# Esquematico_TB66.net
KiCad netlist of a schematic drawn in Altium Designer
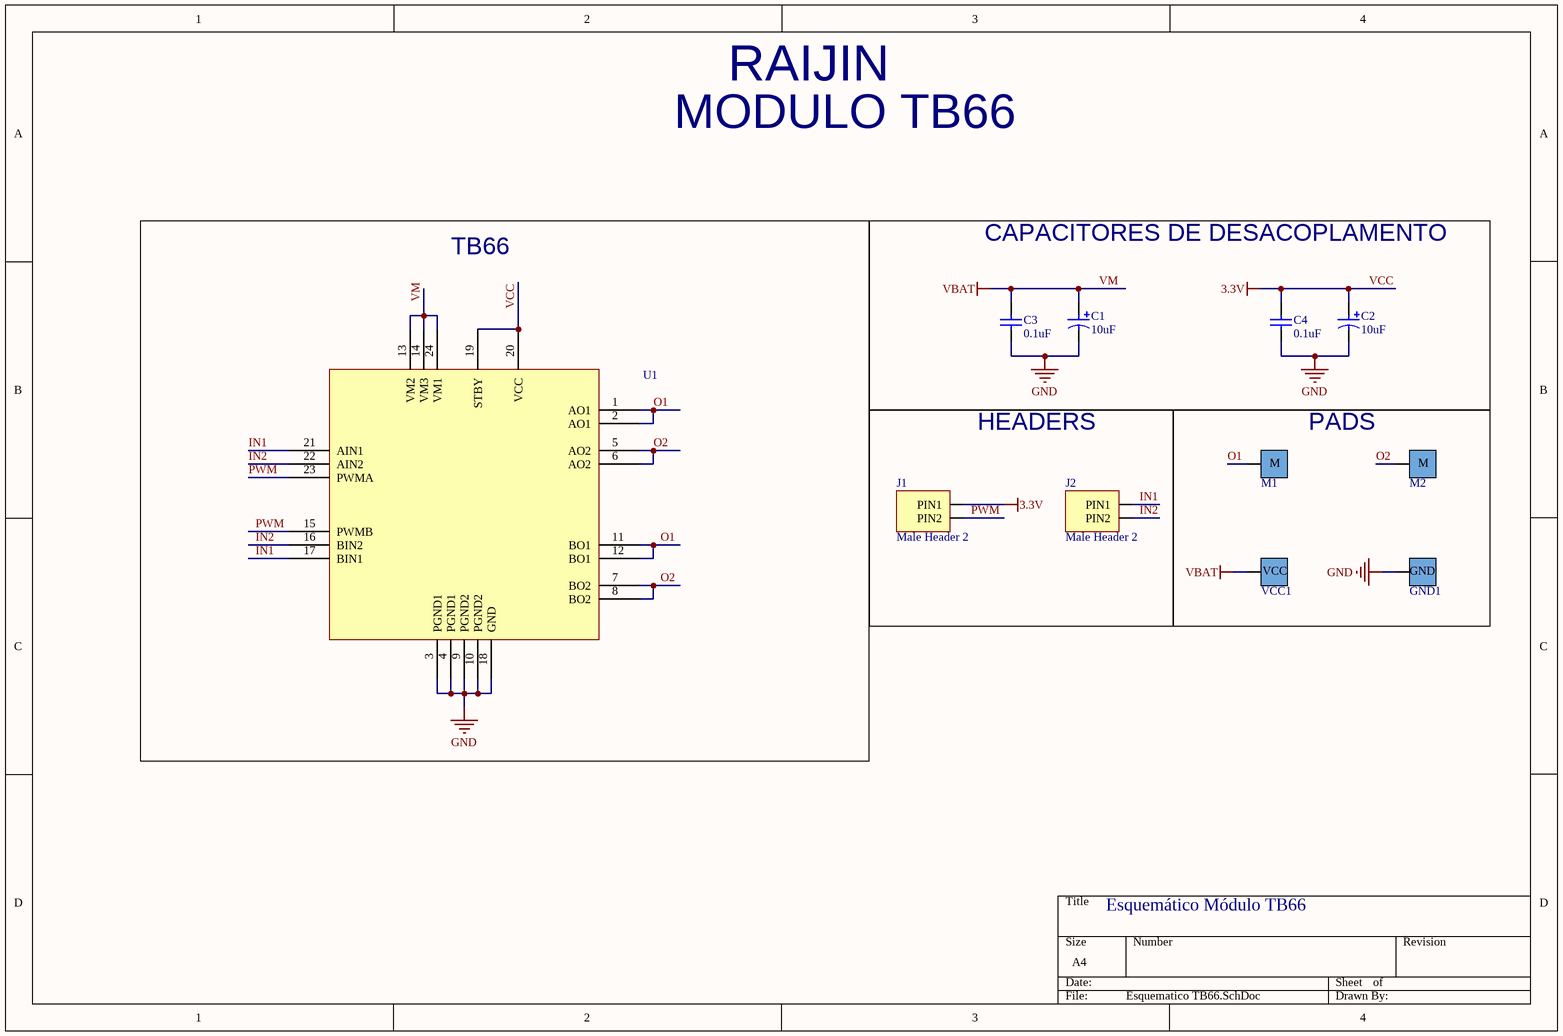
[diagram p0: Esquematico TB66.SchDoc]

(export (version "E")
  (design (tool "Eeschema 10.0.6"))
  (components
    (comp (ref "C1")
      (value "10uF")
      (footprint "TANTALUM C0805")
      (description "CAP TAN 10uF 16V 0805")
      (fields
        (field (name "MANUFACTURER") "AVX")
        (field (name "PART NUMBER") "TACR106K016RTA")
        (field (name "LIBRARY CONTROL - PERSON THAT CHECKED FOOTPRINT") "Nikaum")
        (field (name "LIBRARY CONTROL - PERSON THAT CHECKED SCHEMATIC") "Nikaum")
        (field (name "LIBRARY CONTROL - PERSON THAT DID THE LAST UPDATE FOOTPRINT") "Nikaum")
        (field (name "LIBRARY CONTROL - PERSON THAT DID THE LAST UPDATE SCHEMATIC") "Nikaum")
      )
      (libsource (lib "Uai!Tecas") (part "TACR106K016RTA"))
    )
    (comp (ref "C2")
      (value "10uF")
      (footprint "TANTALUM C0805")
      (description "CAP TAN 10uF 16V 0805")
      (fields
        (field (name "MANUFACTURER") "AVX")
        (field (name "PART NUMBER") "TACR106K016RTA")
        (field (name "LIBRARY CONTROL - PERSON THAT CHECKED FOOTPRINT") "Nikaum")
        (field (name "LIBRARY CONTROL - PERSON THAT CHECKED SCHEMATIC") "Nikaum")
        (field (name "LIBRARY CONTROL - PERSON THAT DID THE LAST UPDATE FOOTPRINT") "Nikaum")
        (field (name "LIBRARY CONTROL - PERSON THAT DID THE LAST UPDATE SCHEMATIC") "Nikaum")
      )
      (libsource (lib "Uai!Tecas") (part "TACR106K016RTA"))
    )
    (comp (ref "C3")
      (value "0.1uF")
      (footprint "C0805")
      (description "CAP CER 0.1uF 25V X7R 0805")
      (fields
        (field (name "MANUFACTURER") "AVX")
        (field (name "PART NUMBER") "08053C104KAT2A")
        (field (name "LIBRARY CONTROL - PERSON THAT CHECKED FOOTPRINT") "Nikaum")
        (field (name "LIBRARY CONTROL - PERSON THAT CHECKED SCHEMATIC") "Nikaum")
        (field (name "LIBRARY CONTROL - PERSON THAT DID THE LAST UPDATE FOOTPRINT") "Nikaum")
        (field (name "LIBRARY CONTROL - PERSON THAT DID THE LAST UPDATE SCHEMATIC") "Nikaum")
      )
      (libsource (lib "Uai!Tecas") (part "08053C104KAT2A"))
    )
    (comp (ref "C4")
      (value "0.1uF")
      (footprint "C0805")
      (description "CAP CER 0.1uF 25V X7R 0805")
      (fields
        (field (name "MANUFACTURER") "AVX")
        (field (name "PART NUMBER") "08053C104KAT2A")
        (field (name "LIBRARY CONTROL - PERSON THAT CHECKED FOOTPRINT") "Nikaum")
        (field (name "LIBRARY CONTROL - PERSON THAT CHECKED SCHEMATIC") "Nikaum")
        (field (name "LIBRARY CONTROL - PERSON THAT DID THE LAST UPDATE FOOTPRINT") "Nikaum")
        (field (name "LIBRARY CONTROL - PERSON THAT DID THE LAST UPDATE SCHEMATIC") "Nikaum")
      )
      (libsource (lib "Uai!Tecas") (part "08053C104KAT2A"))
    )
    (comp (ref "GND1")
      (value "Ground Pad")
      (description "GND PAD MINI SUMÔ")
      (libsource (lib "Uai!Tecas") (part "Ground Pad Mini Sumô"))
    )
    (comp (ref "J1")
      (value "Male Header 2")
      (footprint "MALE HEADER 2")
      (fields
        (field (name "LIBRARY CONTROL - PERSON THAT DID THE LAST UPDATE SCHEMATIC") "Marcos")
        (field (name "LIBRARY CONTROL - PERSONT THAT DID THE LAST UPDATE FOOTPRINT") "Marcos")
      )
      (libsource (lib "Header") (part "Male Header 2"))
    )
    (comp (ref "J2")
      (value "Male Header 2")
      (footprint "MALE HEADER 2")
      (fields
        (field (name "LIBRARY CONTROL - PERSON THAT DID THE LAST UPDATE SCHEMATIC") "Marcos")
        (field (name "LIBRARY CONTROL - PERSONT THAT DID THE LAST UPDATE FOOTPRINT") "Marcos")
      )
      (libsource (lib "Header") (part "Male Header 2"))
    )
    (comp (ref "M1")
      (value "Motor Pad")
      (description "MOTOR PAD MINI SUMÔ")
      (libsource (lib "Uai!Tecas") (part "Motor Pad Mini Sumô"))
    )
    (comp (ref "M2")
      (value "Motor Pad")
      (description "MOTOR PAD MINI SUMÔ")
      (libsource (lib "Uai!Tecas") (part "Motor Pad Mini Sumô"))
    )
    (comp (ref "U1")
      (value "TB6612FNGC8EL")
      (footprint "SSOP-24 (24_pins)")
      (description "IC MTR DRV (2.5V ~ 13.5V) (1A)  SSOP-24")
      (fields
        (field (name "MANUFACTURER") "Toshiba")
        (field (name "LIBRARY CONTROL - PERSON THAT CHECKED SCHEMATIC") "Stéfany (Ster)")
        (field (name "LIBRARY CONTROL - PERSON THAT CHECKED FOOTPRINT") "Stéfany (Ster)")
        (field (name "LIBRARY CONTROL - PERSON THAT DID THE LAST UPDATE SCHEMATIC") "Stéfany (Ster)")
        (field (name "LIBRARY CONTROL - PERSON THAT DID THE LAST UPDATE FOOTPRINT") "Stéfany (Ster)")
      )
      (libsource (lib "Uai!Tecas") (part "TB6612FNGC8EL"))
    )
    (comp (ref "VCC1")
      (value "Source Pad")
      (description "VCC PAD MINI SUMÔ")
      (libsource (lib "Uai!Tecas") (part "Source Pad Mini Sumô"))
    )
  )
  (nets
    (net (code "1") (name "/IN1") (class "Default")
      (node (ref "J2") (pin "PIN1") (pinfunction "PIN1_PIN1") (pintype "passive"))
      (node (ref "U1") (pin "17") (pinfunction "BIN1_17") (pintype "passive"))
      (node (ref "U1") (pin "21") (pinfunction "AIN1_21") (pintype "passive"))
    )
    (net (code "2") (name "/IN2") (class "Default")
      (node (ref "J2") (pin "PIN2") (pinfunction "PIN2_PIN2") (pintype "passive"))
      (node (ref "U1") (pin "16") (pinfunction "BIN2_16") (pintype "passive"))
      (node (ref "U1") (pin "22") (pinfunction "AIN2_22") (pintype "passive"))
    )
    (net (code "3") (name "/O1") (class "Default")
      (node (ref "M1") (pin "M") (pinfunction "M_M") (pintype "passive"))
      (node (ref "U1") (pin "1") (pinfunction "AO1_1") (pintype "passive"))
      (node (ref "U1") (pin "11") (pinfunction "BO1_11") (pintype "passive"))
      (node (ref "U1") (pin "12") (pinfunction "BO1_12") (pintype "passive"))
      (node (ref "U1") (pin "2") (pinfunction "AO1_2") (pintype "passive"))
    )
    (net (code "4") (name "/O2") (class "Default")
      (node (ref "M2") (pin "M") (pinfunction "M_M") (pintype "passive"))
      (node (ref "U1") (pin "5") (pinfunction "AO2_5") (pintype "passive"))
      (node (ref "U1") (pin "6") (pinfunction "AO2_6") (pintype "passive"))
      (node (ref "U1") (pin "7") (pinfunction "BO2_7") (pintype "passive"))
      (node (ref "U1") (pin "8") (pinfunction "BO2_8") (pintype "passive"))
    )
    (net (code "5") (name "/PWM") (class "Default")
      (node (ref "J1") (pin "PIN2") (pinfunction "PIN2_PIN2") (pintype "passive"))
      (node (ref "U1") (pin "15") (pinfunction "PWMB_15") (pintype "passive"))
      (node (ref "U1") (pin "23") (pinfunction "PWMA_23") (pintype "passive"))
    )
    (net (code "6") (name "3.3V") (class "Default")
      (node (ref "C2") (pin "1") (pinfunction "1_1") (pintype "passive"))
      (node (ref "C4") (pin "2") (pinfunction "2_2") (pintype "passive"))
      (node (ref "J1") (pin "PIN1") (pinfunction "PIN1_PIN1") (pintype "passive"))
      (node (ref "U1") (pin "19") (pinfunction "STBY_19") (pintype "passive"))
      (node (ref "U1") (pin "20") (pinfunction "VCC_20") (pintype "passive"))
    )
    (net (code "7") (name "GND") (class "Default")
      (node (ref "C1") (pin "2") (pinfunction "2_2") (pintype "passive"))
      (node (ref "C2") (pin "2") (pinfunction "2_2") (pintype "passive"))
      (node (ref "C3") (pin "1") (pinfunction "1_1") (pintype "passive"))
      (node (ref "C4") (pin "1") (pinfunction "1_1") (pintype "passive"))
      (node (ref "GND1") (pin "A") (pinfunction "GND_A") (pintype "passive"))
      (node (ref "U1") (pin "10") (pinfunction "PGND2_10") (pintype "passive"))
      (node (ref "U1") (pin "18") (pinfunction "GND_18") (pintype "passive"))
      (node (ref "U1") (pin "3") (pinfunction "PGND1_3") (pintype "passive"))
      (node (ref "U1") (pin "4") (pinfunction "PGND1_4") (pintype "passive"))
      (node (ref "U1") (pin "9") (pinfunction "PGND2_9") (pintype "passive"))
    )
    (net (code "8") (name "VBAT") (class "Default")
      (node (ref "C1") (pin "1") (pinfunction "1_1") (pintype "passive"))
      (node (ref "C3") (pin "2") (pinfunction "2_2") (pintype "passive"))
      (node (ref "U1") (pin "13") (pinfunction "VM2_13") (pintype "passive"))
      (node (ref "U1") (pin "14") (pinfunction "VM3_14") (pintype "passive"))
      (node (ref "U1") (pin "24") (pinfunction "VM1_24") (pintype "passive"))
      (node (ref "VCC1") (pin "A") (pinfunction "VCC_A") (pintype "passive"))
    )
  )
)
